# SRAM.net
KiCad netlist of a schematic drawn in Altium Designer
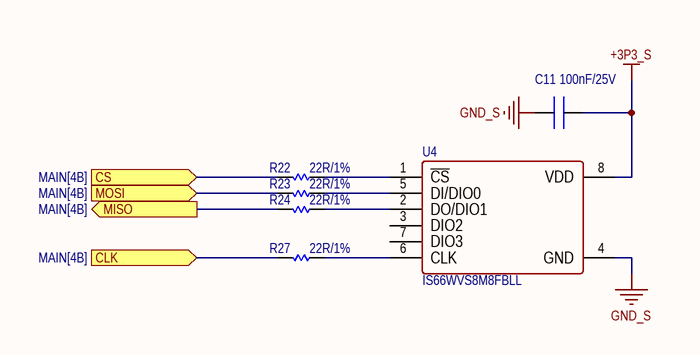
[diagram p0: SRAM.SchDoc]

(export (version "E")
  (design (tool "Eeschema 10.0.6"))
  (components
    (comp (ref "C11")
      (value "100nF/25V")
      (footprint "CN-SMD-0603")
      (description "CL10B104KA8NNNC")
      (libsource (lib "Library") (part "CN"))
    )
    (comp (ref "R22")
      (value "22R/1%")
      (footprint "RES-SMD-0603")
      (description "ERJ-3EKF22R0V")
      (fields
        (field (name "MANUFACTURER") "Generic Components")
        (field (name "PUBLISHER") "Altium Hobart Technology Centre")
      )
      (libsource (lib "Library") (part "Res-SMD"))
    )
    (comp (ref "R23")
      (value "22R/1%")
      (footprint "RES-SMD-0603")
      (description "ERJ-3EKF22R0V")
      (fields
        (field (name "MANUFACTURER") "Generic Components")
        (field (name "PUBLISHER") "Altium Hobart Technology Centre")
      )
      (libsource (lib "Library") (part "Res-SMD"))
    )
    (comp (ref "R24")
      (value "22R/1%")
      (footprint "RES-SMD-0603")
      (description "ERJ-3EKF22R0V")
      (fields
        (field (name "MANUFACTURER") "Generic Components")
        (field (name "PUBLISHER") "Altium Hobart Technology Centre")
      )
      (libsource (lib "Library") (part "Res-SMD"))
    )
    (comp (ref "R27")
      (value "22R/1%")
      (footprint "RES-SMD-0603")
      (description "ERJ-3EKF22R0V")
      (fields
        (field (name "MANUFACTURER") "Generic Components")
        (field (name "PUBLISHER") "Altium Hobart Technology Centre")
      )
      (libsource (lib "Library") (part "Res-SMD"))
    )
    (comp (ref "U4")
      (value "IS66WVS8M8FBLL")
      (footprint "SO8")
      (description "64Mb SerialRAM 1.8V/3.0V, 104MHZ, SPI & QPI PROTOCOL")
      (libsource (lib "Library") (part "IS66WVS8M8FBLL"))
    )
  )
  (nets
    (net (code "1") (name "+3P3_S") (class "Default")
      (node (ref "C11") (pin "2") (pinfunction "2_2") (pintype "passive"))
      (node (ref "U4") (pin "8") (pinfunction "VDD_8") (pintype "passive"))
    )
    (net (code "2") (name "/CLK") (class "Default")
      (node (ref "R27") (pin "2") (pinfunction "2_2") (pintype "passive"))
    )
    (net (code "3") (name "/CS") (class "Default")
      (node (ref "R22") (pin "2") (pinfunction "2_2") (pintype "passive"))
    )
    (net (code "4") (name "/MISO") (class "Default")
      (node (ref "R24") (pin "2") (pinfunction "2_2") (pintype "passive"))
    )
    (net (code "5") (name "/MOSI") (class "Default")
      (node (ref "R23") (pin "2") (pinfunction "2_2") (pintype "passive"))
    )
    (net (code "6") (name "GND_S") (class "Default")
      (node (ref "C11") (pin "1") (pinfunction "1_1") (pintype "passive"))
      (node (ref "U4") (pin "4") (pinfunction "GND_4") (pintype "passive"))
    )
    (net (code "7") (name "Net-(U4-CLK)") (class "Default")
      (node (ref "R27") (pin "1") (pinfunction "1_1") (pintype "passive"))
      (node (ref "U4") (pin "6") (pinfunction "CLK_6") (pintype "passive"))
    )
    (net (code "8") (name "Net-(U4-DI{slash}DIO0)") (class "Default")
      (node (ref "R23") (pin "1") (pinfunction "1_1") (pintype "passive"))
      (node (ref "U4") (pin "5") (pinfunction "DI/DIO0_5") (pintype "passive"))
    )
    (net (code "9") (name "Net-(U4-DO{slash}DIO1)") (class "Default")
      (node (ref "R24") (pin "1") (pinfunction "1_1") (pintype "passive"))
      (node (ref "U4") (pin "2") (pinfunction "DO/DIO1_2") (pintype "passive"))
    )
    (net (code "10") (name "Net-(U4-~{CS})") (class "Default")
      (node (ref "R22") (pin "1") (pinfunction "1_1") (pintype "passive"))
      (node (ref "U4") (pin "1") (pinfunction "~{CS}_1") (pintype "passive"))
    )
    (net (code "11") (name "unconnected-(U4-DIO2-Pad3)") (class "Default")
      (node (ref "U4") (pin "3") (pinfunction "DIO2_3") (pintype "passive"))
    )
    (net (code "12") (name "unconnected-(U4-DIO3-Pad7)") (class "Default")
      (node (ref "U4") (pin "7") (pinfunction "DIO3_7") (pintype "passive"))
    )
  )
)
